# design.net
KiCad netlist of a schematic drawn in Altium Designer
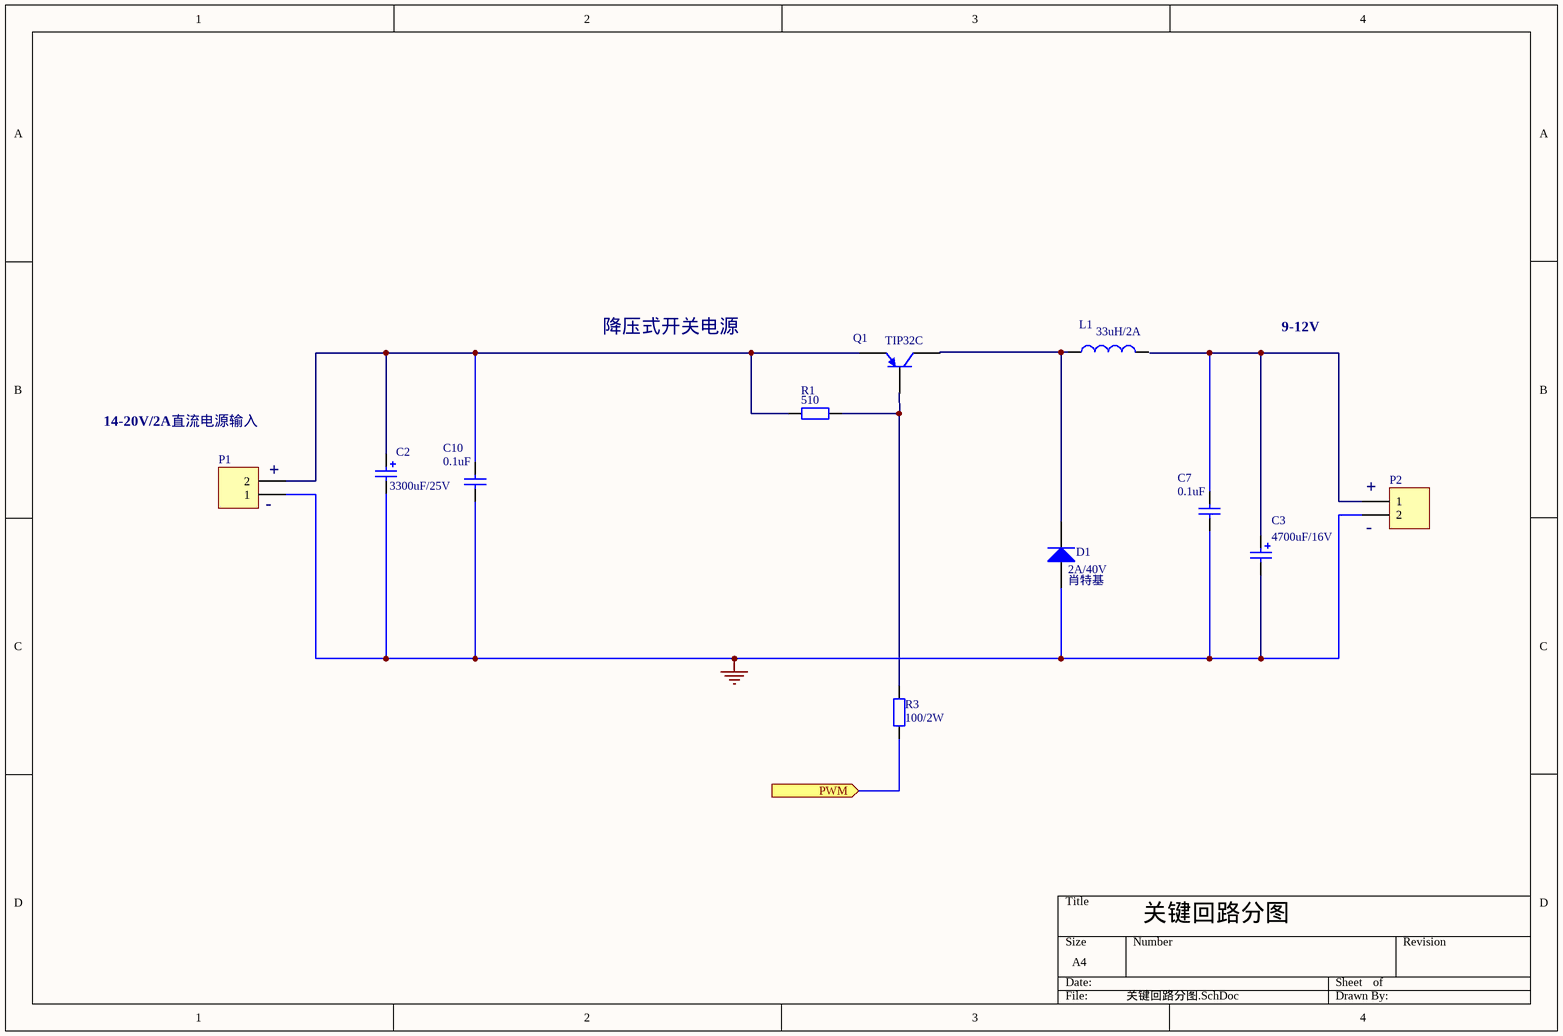
[diagram p0: 关键回路分图.SchDoc]

(export (version "E")
  (design (tool "Eeschema 10.0.6"))
  (components
    (comp (ref "C2")
      (value "3300uF/25V")
      (footprint "3300电解电容")
      (description "Polarized Capacitor (Axial)")
      (fields (field (name "Comment") "Cap Pol2") (field (name "PUBLISHER") "Altium Limited"))
      (libsource (lib "Miscellaneous Devices") (part "Cap Pol2"))
    )
    (comp (ref "C3")
      (value "4700uF/16V")
      (footprint "4700电解电容")
      (description "Polarized Capacitor (Axial)")
      (fields (field (name "Comment") "Cap Pol2") (field (name "PUBLISHER") "Altium Limited"))
      (libsource (lib "Miscellaneous Devices") (part "Cap Pol2"))
    )
    (comp (ref "C7")
      (value "0.1uF")
      (footprint "瓷片电容")
      (description "Capacitor")
      (fields (field (name "Comment") "Cap") (field (name "PUBLISHER") "Altium Limited"))
      (libsource (lib "Miscellaneous Devices") (part "Cap"))
    )
    (comp (ref "C10")
      (value "0.1uF")
      (footprint "瓷片电容")
      (description "Capacitor")
      (fields (field (name "Comment") "Cap") (field (name "PUBLISHER") "Altium Limited"))
      (libsource (lib "Miscellaneous Devices") (part "Cap"))
    )
    (comp (ref "D1")
      (value "2A/40V")
      (footprint "肖特基")
      (description "Default Diode")
      (fields (field (name "PACKAGEREFERENCE") "肖特基") (field (name "PUBLISHER") "Altium Limited"))
      (libsource (lib "Miscellaneous Devices") (part "Diode"))
    )
    (comp (ref "L1")
      (value "33uH/2A")
      (footprint "电感实物")
      (description "Inductor")
      (fields (field (name "PUBLISHER") "Altium Limited"))
      (libsource (lib "Miscellaneous Devices") (part "Inductor"))
    )
    (comp (ref "P1")
      (value "Header 2")
      (footprint "HDR1X2")
      (description "Header, 2-Pin")
      (fields (field (name "PUBLISHER") "Altium Limited"))
      (libsource (lib "") (part "Header 2_1"))
    )
    (comp (ref "P2")
      (value "Header 2")
      (footprint "HDR1X2")
      (description "Header, 2-Pin")
      (fields (field (name "PUBLISHER") "Altium Limited"))
      (libsource (lib "Miscellaneous Connectors") (part "Header 2"))
    )
    (comp (ref "R1")
      (value "510")
      (footprint "AXIAL-0.4")
      (description "Resistor")
      (fields (field (name "Comment") "Res2") (field (name "PUBLISHER") "Altium Limited"))
      (libsource (lib "") (part "Res2_1"))
    )
    (comp (ref "R3")
      (value "100/2W")
      (footprint "AXIAL-0.4")
      (description "Resistor")
      (fields (field (name "Comment") "Res2") (field (name "PUBLISHER") "Altium Limited"))
      (libsource (lib "Miscellaneous Devices") (part "Res2"))
    )
    (comp (ref "TIP32C")
      (value "Q1")
      (footprint "TO-220-AB")
      (description "PNP Bipolar Transistor")
      (fields (field (name "PUBLISHER") "Altium Limited"))
      (libsource (lib "Miscellaneous Devices") (part "PNP"))
    )
  )
  (nets
    (net (code "1") (name "/PWM") (class "Default")
      (node (ref "R3") (pin "1") (pinfunction "1_1") (pintype "passive"))
    )
    (net (code "2") (name "GND") (class "Default")
      (node (ref "C10") (pin "1") (pinfunction "1_1") (pintype "passive"))
      (node (ref "C2") (pin "2") (pinfunction "2_2") (pintype "passive"))
      (node (ref "C3") (pin "2") (pinfunction "2_2") (pintype "passive"))
      (node (ref "C7") (pin "1") (pinfunction "1_1") (pintype "passive"))
      (node (ref "D1") (pin "1") (pinfunction "A_1") (pintype "passive"))
      (node (ref "P1") (pin "1") (pinfunction "1_1") (pintype "passive"))
      (node (ref "P2") (pin "2") (pinfunction "2_2") (pintype "passive"))
    )
    (net (code "3") (name "Net-(C3-Pad1)") (class "Default")
      (node (ref "C3") (pin "1") (pinfunction "1_1") (pintype "passive"))
      (node (ref "C7") (pin "2") (pinfunction "2_2") (pintype "passive"))
      (node (ref "P2") (pin "1") (pinfunction "1_1") (pintype "passive"))
    )
    (net (code "4") (name "Net-(D1-K)") (class "Default")
      (node (ref "D1") (pin "2") (pinfunction "K_2") (pintype "passive"))
      (node (ref "L1") (pin "1") (pinfunction "1_1") (pintype "passive"))
    )
    (net (code "5") (name "Net-(R1-Pad2)") (class "Default")
      (node (ref "R1") (pin "2") (pinfunction "2_2") (pintype "passive"))
      (node (ref "R3") (pin "2") (pinfunction "2_2") (pintype "passive"))
    )
    (net (code "6") (name "Net-(TIP32C-E)") (class "Default")
      (node (ref "C10") (pin "2") (pinfunction "2_2") (pintype "passive"))
      (node (ref "C2") (pin "1") (pinfunction "1_1") (pintype "passive"))
      (node (ref "P1") (pin "2") (pinfunction "2_2") (pintype "passive"))
      (node (ref "R1") (pin "1") (pinfunction "1_1") (pintype "passive"))
      (node (ref "TIP32C") (pin "3") (pinfunction "E_3") (pintype "passive"))
    )
    (net (code "7") (name "unconnected-(L1-Pad2)") (class "Default")
      (node (ref "L1") (pin "2") (pinfunction "2_2") (pintype "passive"))
    )
    (net (code "8") (name "unconnected-(TIP32C-B-Pad2)") (class "Default")
      (node (ref "TIP32C") (pin "2") (pinfunction "B_2") (pintype "passive"))
    )
    (net (code "9") (name "unconnected-(TIP32C-C-Pad1)") (class "Default")
      (node (ref "TIP32C") (pin "1") (pinfunction "C_1") (pintype "passive"))
    )
  )
)
